# DAPbench-LPC11U35-v1_0_0.net
KiCad netlist of a schematic drawn in EAGLE
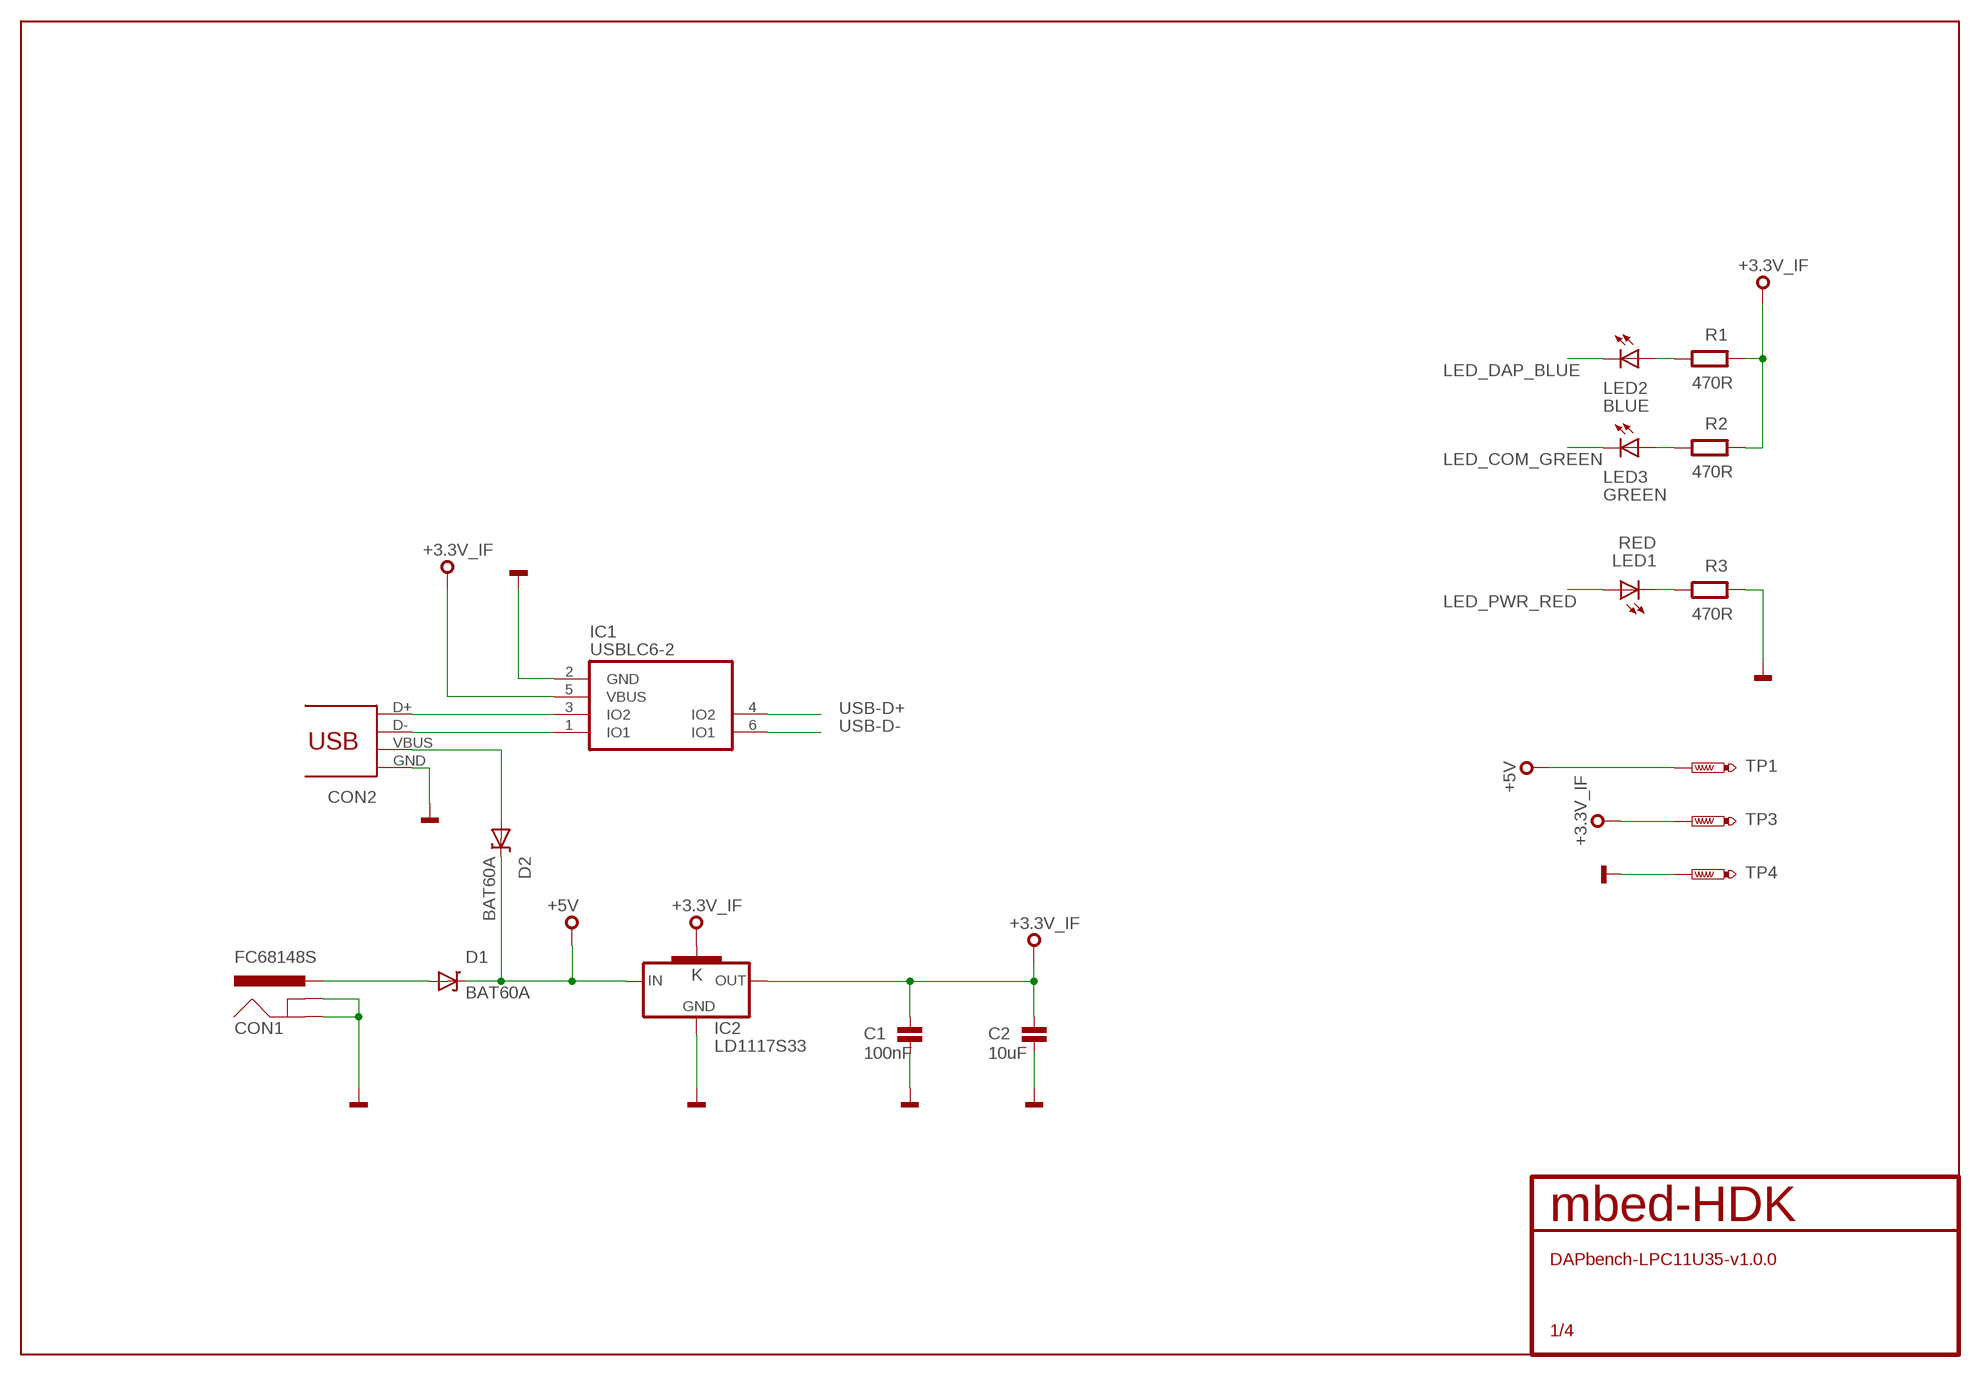
[diagram p0: schematic, sheet 1]
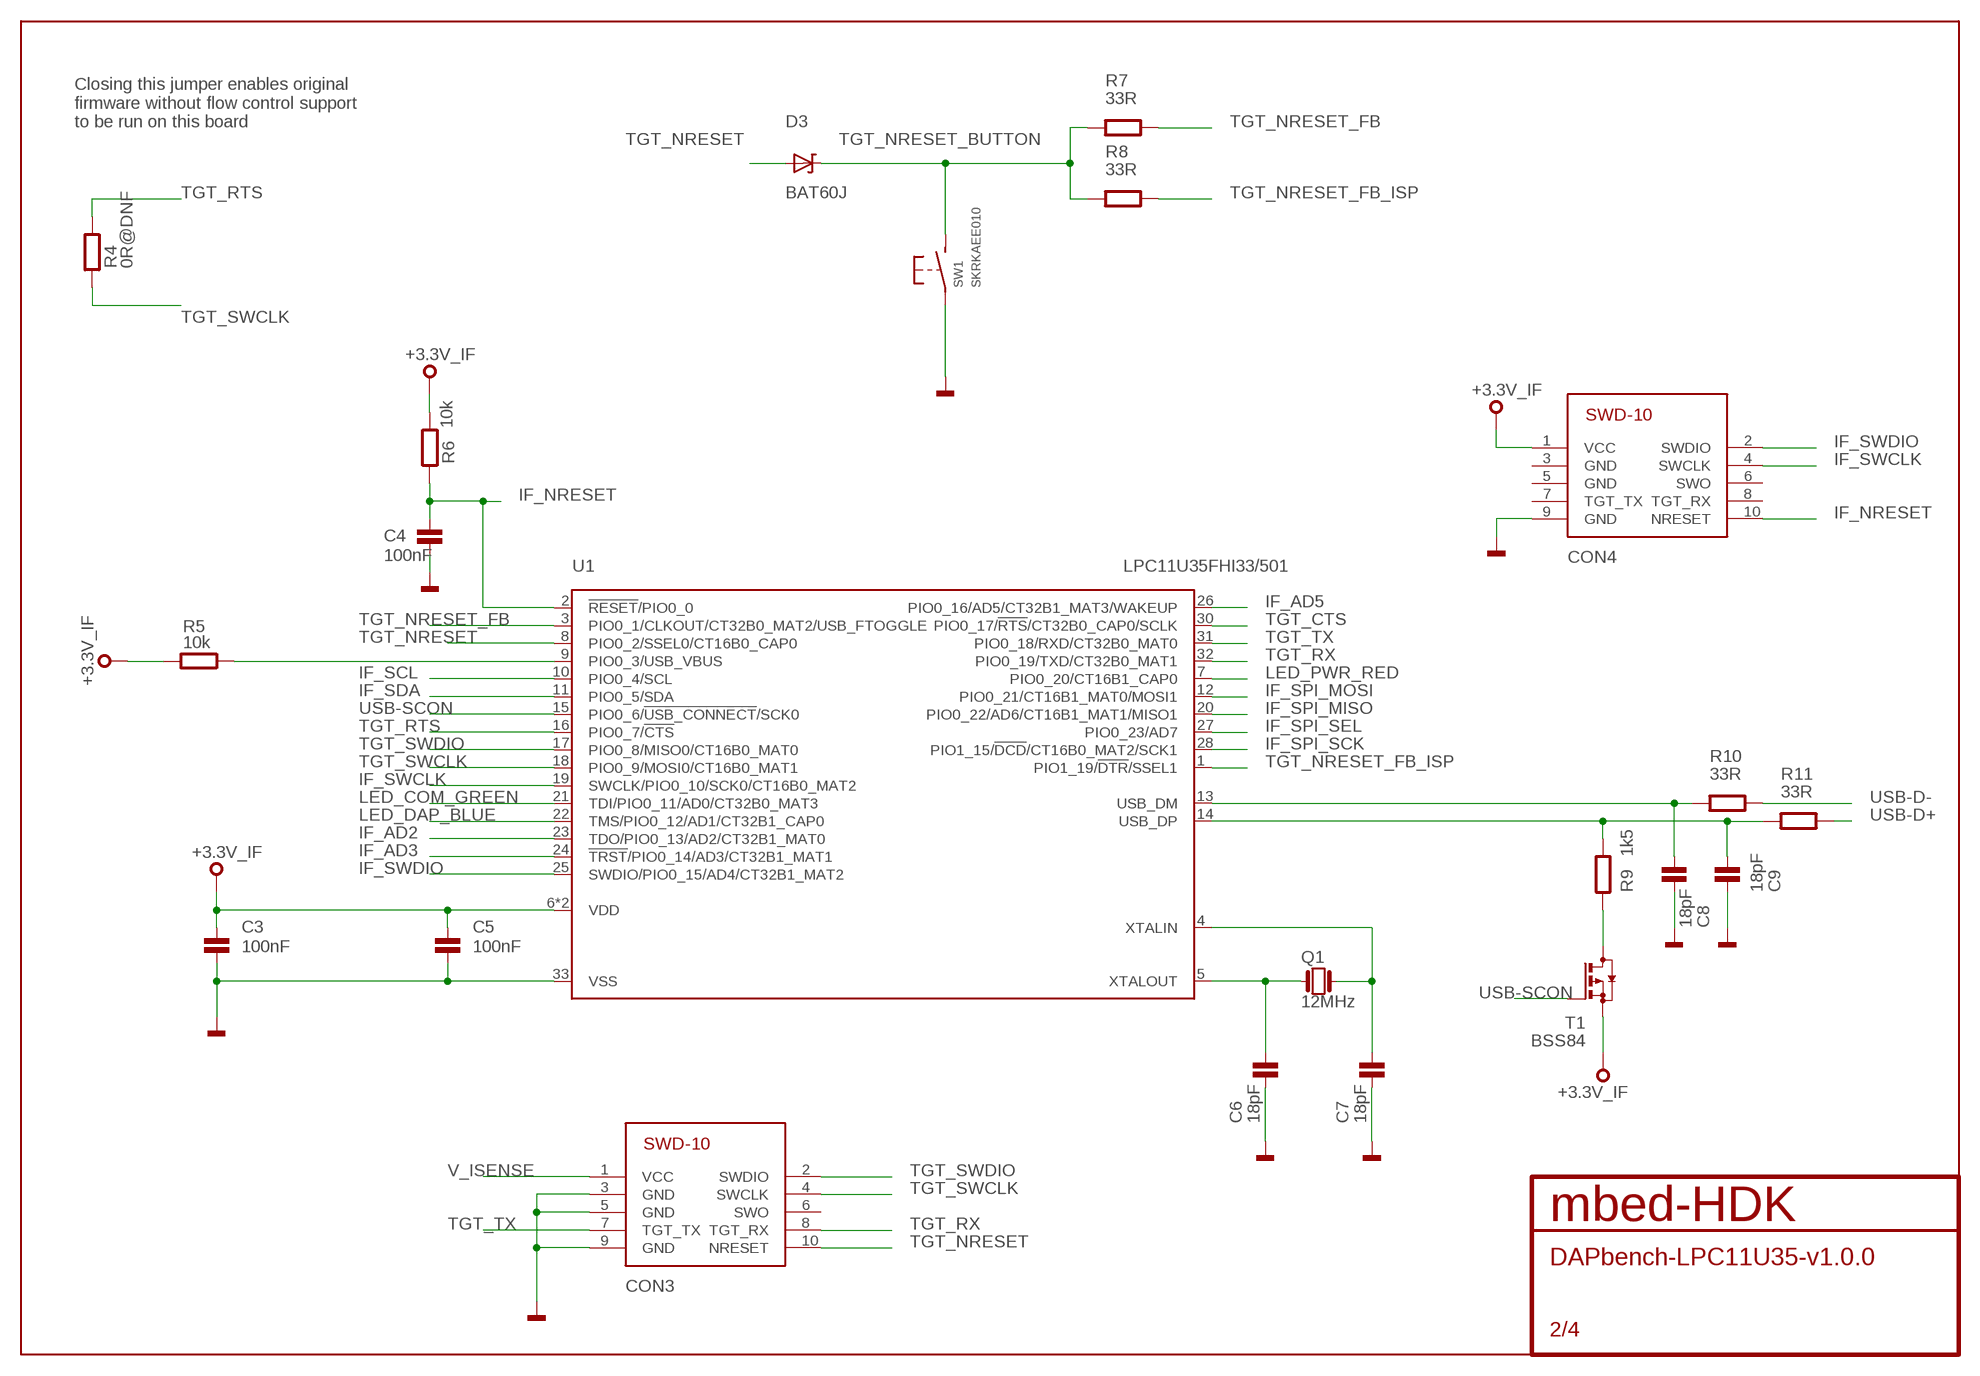
[diagram p1: schematic, sheet 2]
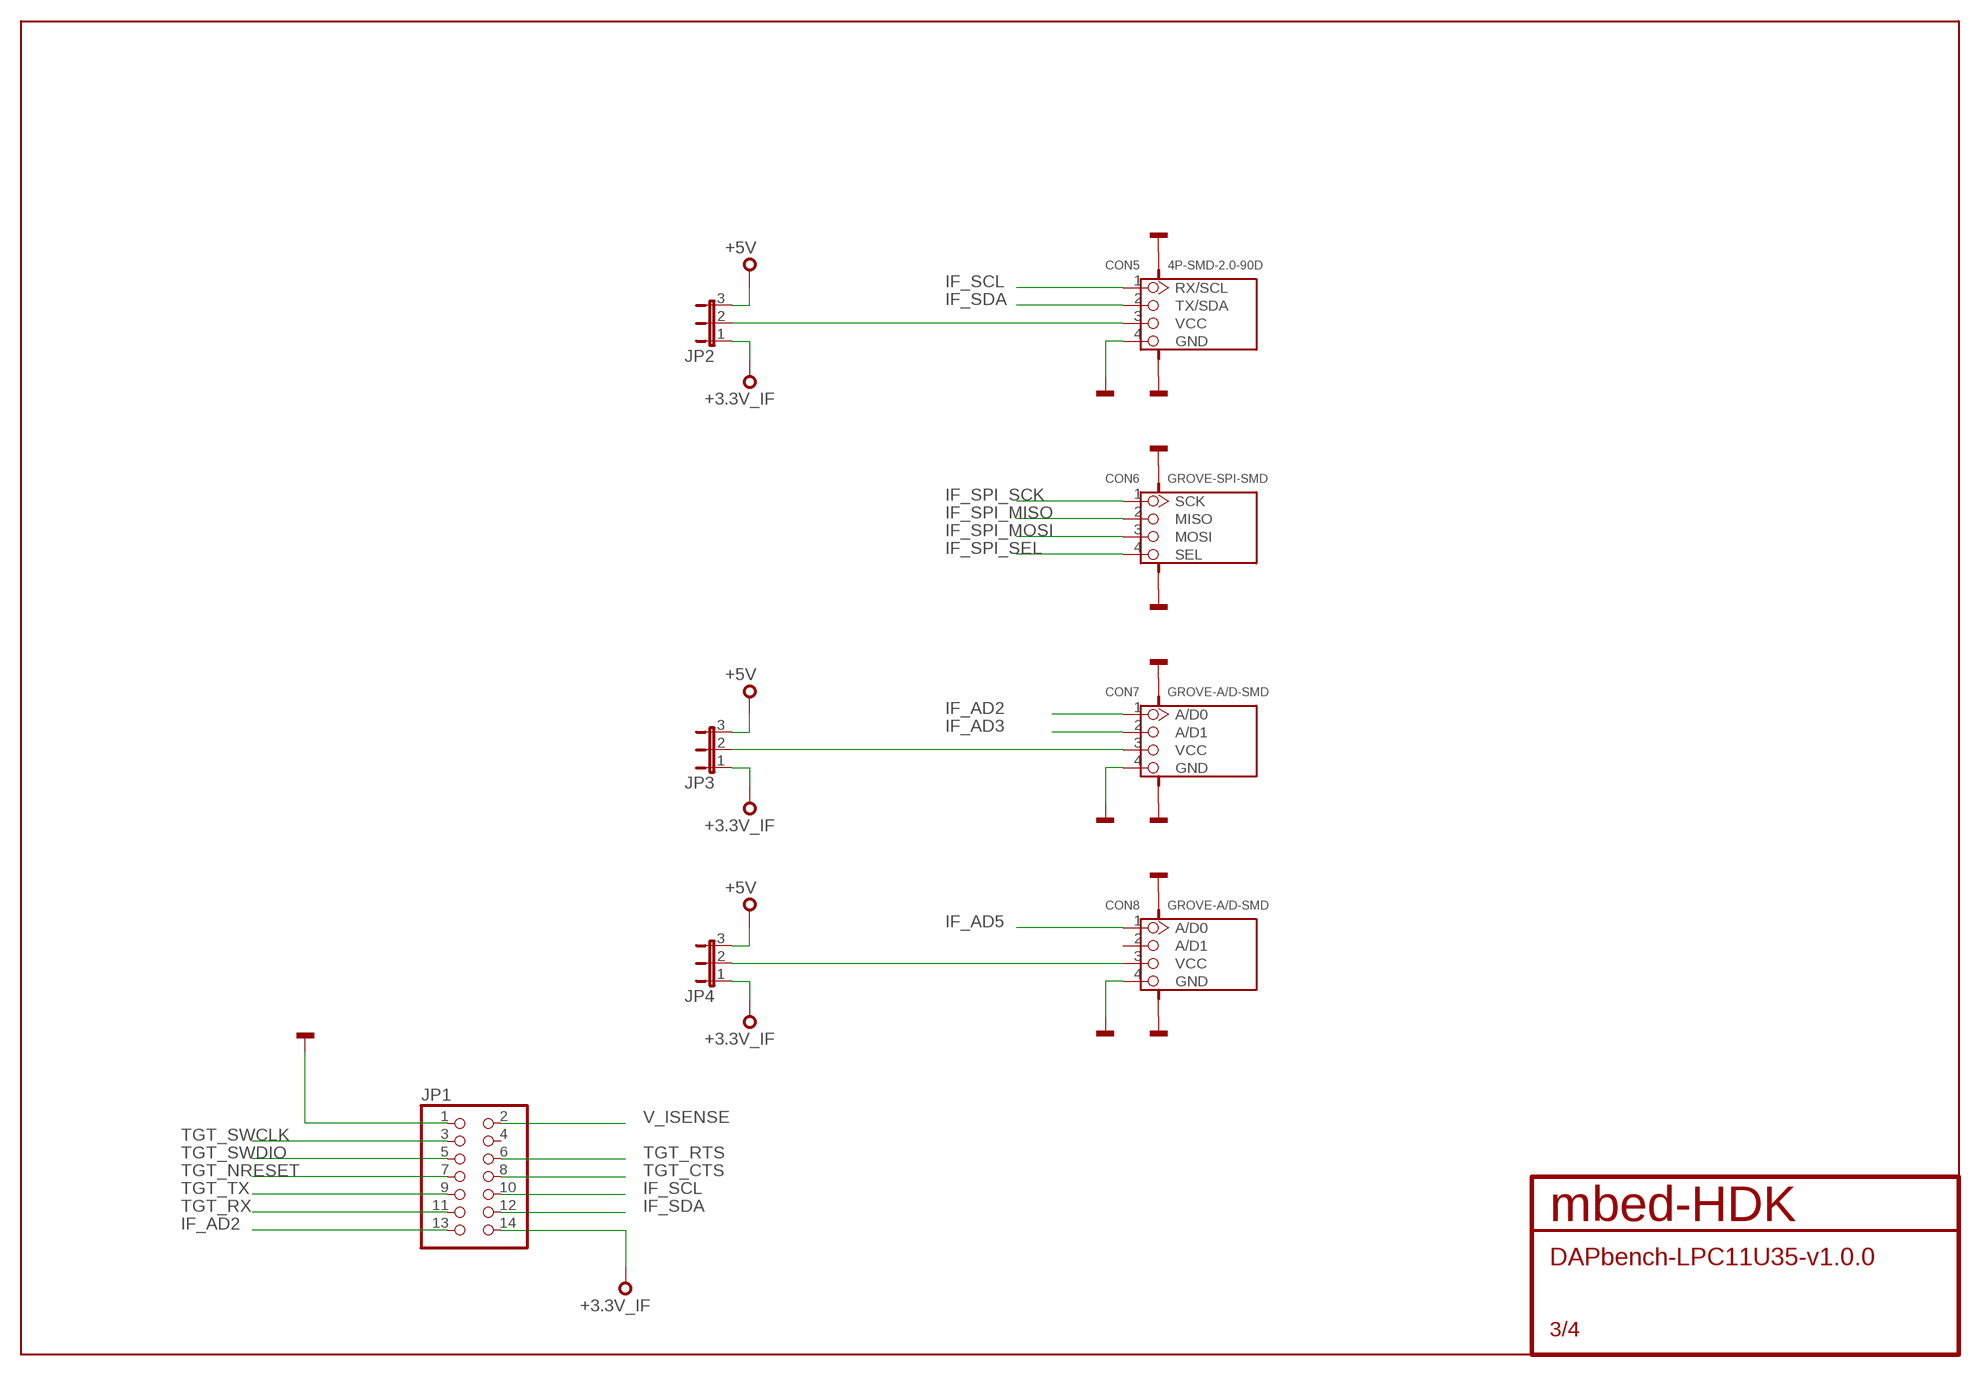
[diagram p2: schematic, sheet 3]
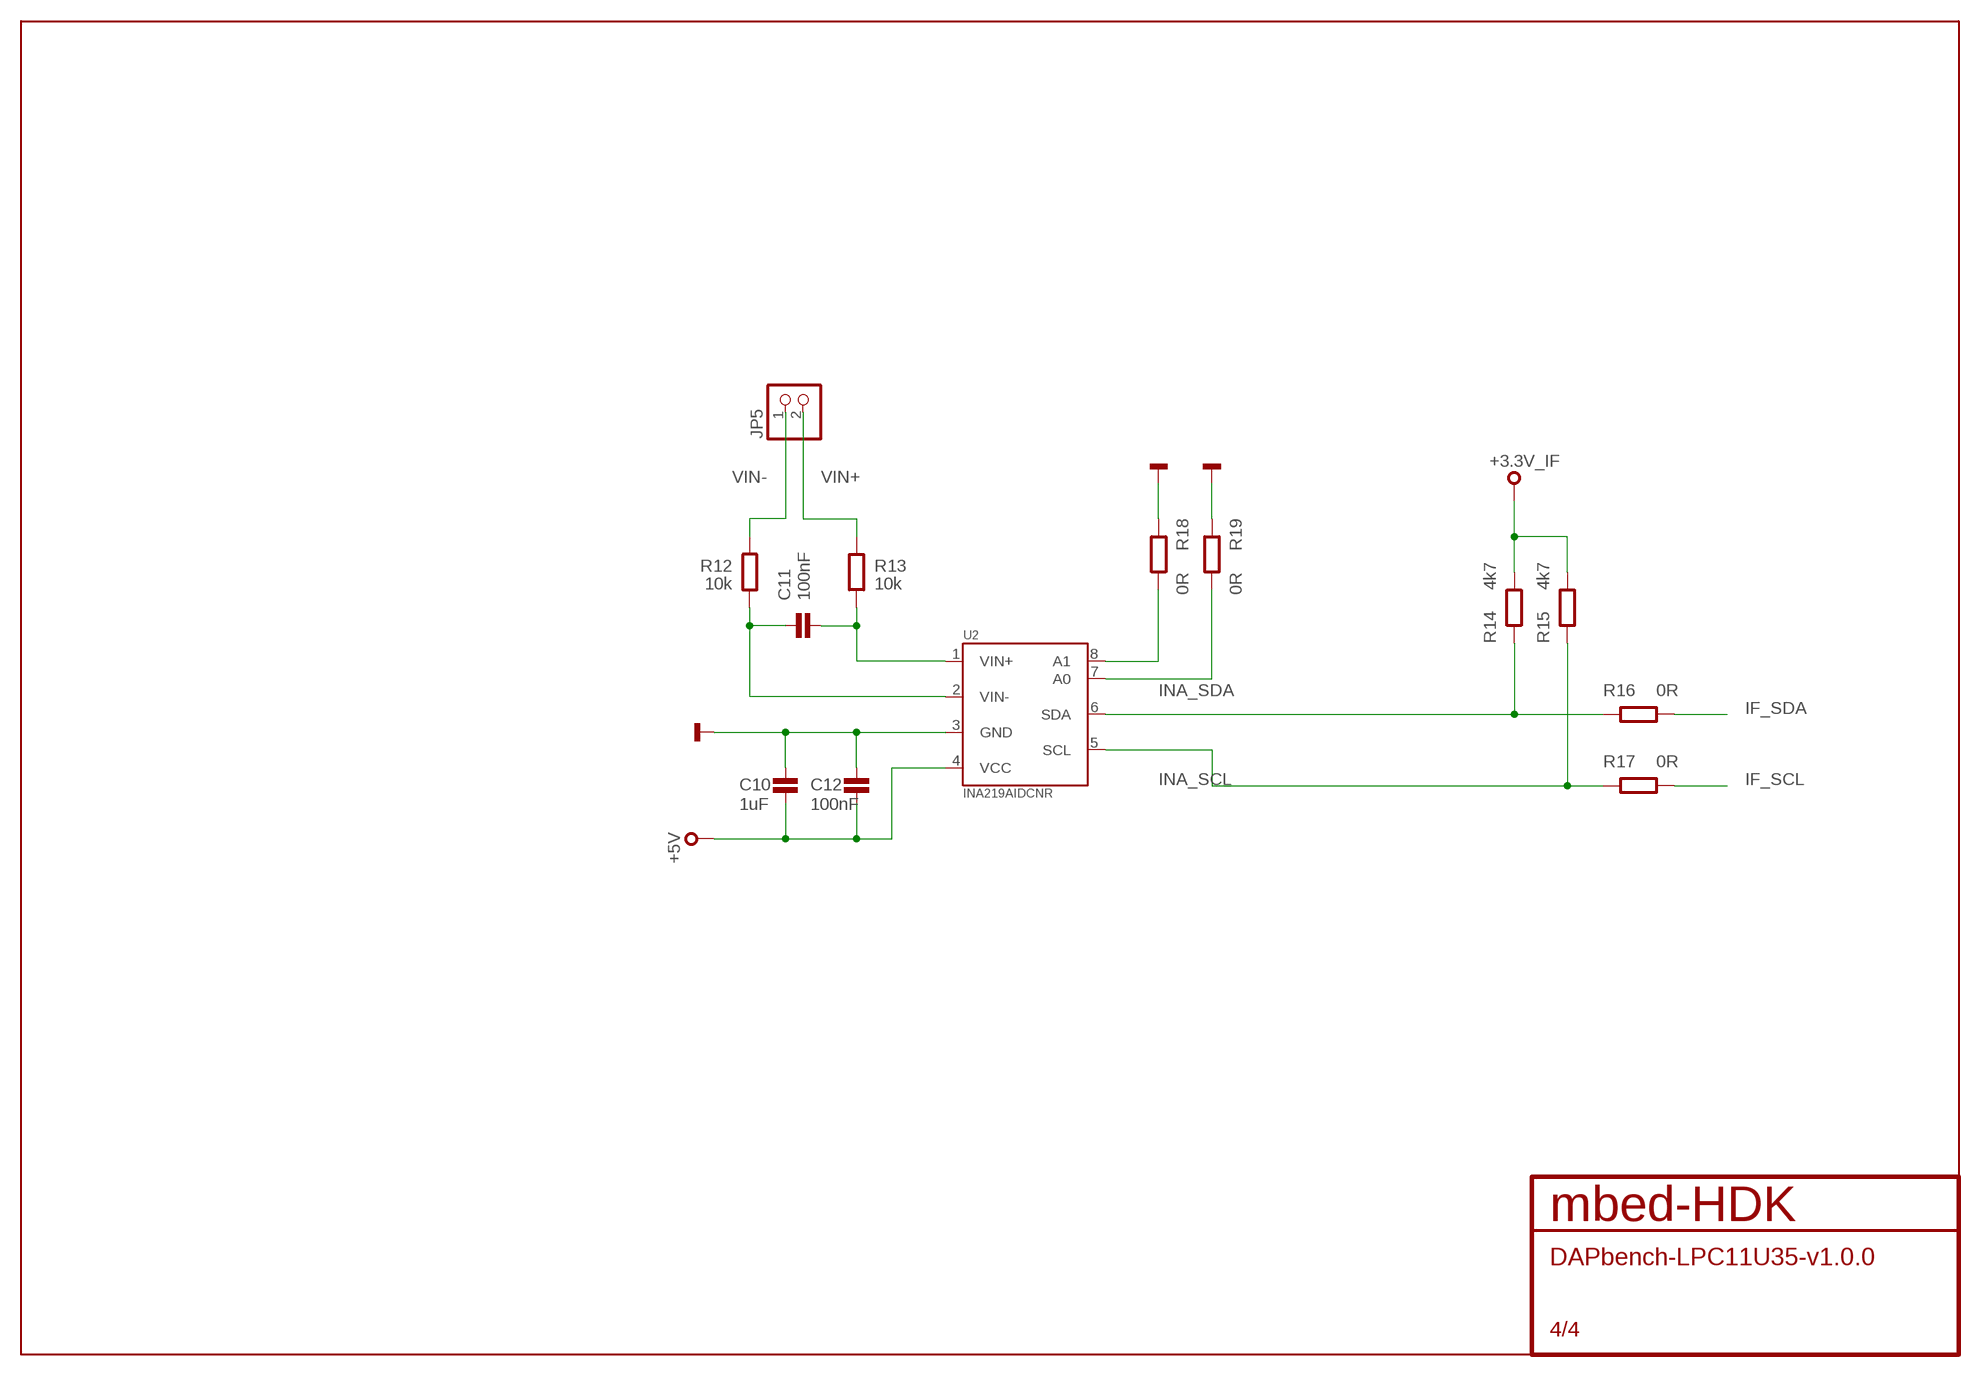
[diagram p3: schematic, sheet 4]

(export (version "E")
  (design (tool "Eeschema 10.0.6"))
  (components
    (comp (ref "C10")
      (value "1uF")
      (footprint "eagle-import:0603")
      (libsource (lib "eagle-import") (part "C0603"))
    )
    (comp (ref "C11")
      (value "100nF")
      (footprint "eagle-import:0603")
      (libsource (lib "eagle-import") (part "C0603"))
    )
    (comp (ref "C12")
      (value "100nF")
      (footprint "eagle-import:0603")
      (libsource (lib "eagle-import") (part "C0603"))
    )
    (comp (ref "JP5")
      (value "PINHD-1X2")
      (footprint "eagle-import:1X02")
      (libsource (lib "eagle-import") (part "PINHD-1X2"))
    )
    (comp (ref "R12")
      (value "10k")
      (footprint "eagle-import:0603@1")
      (libsource (lib "eagle-import") (part "R0603"))
    )
    (comp (ref "R13")
      (value "10k")
      (footprint "eagle-import:0603@1")
      (libsource (lib "eagle-import") (part "R0603"))
    )
    (comp (ref "R14")
      (value "4k7")
      (footprint "eagle-import:0603@1")
      (libsource (lib "eagle-import") (part "R0603"))
    )
    (comp (ref "R15")
      (value "4k7")
      (footprint "eagle-import:0603@1")
      (libsource (lib "eagle-import") (part "R0603"))
    )
    (comp (ref "R16")
      (value "0R")
      (footprint "eagle-import:0603@1")
      (libsource (lib "eagle-import") (part "R0603"))
    )
    (comp (ref "R17")
      (value "0R")
      (footprint "eagle-import:0603@1")
      (libsource (lib "eagle-import") (part "R0603"))
    )
    (comp (ref "R18")
      (value "0R")
      (footprint "eagle-import:0603@1")
      (libsource (lib "eagle-import") (part "R0603"))
    )
    (comp (ref "R19")
      (value "0R")
      (footprint "eagle-import:0603@1")
      (libsource (lib "eagle-import") (part "R0603"))
    )
    (comp (ref "U2")
      (value "INA219AIDCNR")
      (footprint "eagle-import:SOT23-8")
      (fields (field (name "MF") "Texas Instruments"))
      (libsource (lib "eagle-import") (part "INA219AIDCNR"))
    )
    (comp (ref "C1")
      (value "100nF")
      (footprint "eagle-import:0603")
      (libsource (lib "eagle-import") (part "C0603"))
    )
    (comp (ref "C2")
      (value "10uF")
      (footprint "eagle-import:0603")
      (libsource (lib "eagle-import") (part "C0603"))
    )
    (comp (ref "CON1")
      (value "FC68148S")
      (footprint "eagle-import:FC68148S")
      (fields (field (name "MF") "Cliff"))
      (libsource (lib "eagle-import") (part "FC68148S"))
    )
    (comp (ref "CON2")
      (value "USB_MICROB")
      (footprint "eagle-import:MOLEX-47364-0001")
      (libsource (lib "eagle-import") (part "USB_MICROB"))
    )
    (comp (ref "D1")
      (value "BAT60A")
      (footprint "eagle-import:SOD323")
      (fields (field (name "MF") "Infineon"))
      (libsource (lib "eagle-import") (part "mbed-HDK-Transistor_BAT60A"))
    )
    (comp (ref "D2")
      (value "BAT60A")
      (footprint "eagle-import:SOD323")
      (fields (field (name "MF") "Infineon"))
      (libsource (lib "eagle-import") (part "mbed-HDK-Transistor_BAT60A"))
    )
    (comp (ref "IC1")
      (value "USBLC6-2SC6")
      (footprint "eagle-import:SOT23-6L")
      (libsource (lib "eagle-import") (part "USBLC6-2SC6"))
    )
    (comp (ref "IC2")
      (value "LD1117S33")
      (footprint "eagle-import:SOT223")
      (libsource (lib "eagle-import") (part "LD1117S33"))
    )
    (comp (ref "LED1")
      (value "RED")
      (footprint "eagle-import:CHIPLED_0603")
      (libsource (lib "eagle-import") (part "LED0603"))
    )
    (comp (ref "LED2")
      (value "BLUE")
      (footprint "eagle-import:CHIPLED_0603")
      (libsource (lib "eagle-import") (part "LED0603"))
    )
    (comp (ref "LED3")
      (value "GREEN")
      (footprint "eagle-import:CHIPLED_0603")
      (libsource (lib "eagle-import") (part "LED0603"))
    )
    (comp (ref "R1")
      (value "470R")
      (footprint "eagle-import:0603@1")
      (libsource (lib "eagle-import") (part "R0603"))
    )
    (comp (ref "R2")
      (value "470R")
      (footprint "eagle-import:0603@1")
      (libsource (lib "eagle-import") (part "R0603"))
    )
    (comp (ref "R3")
      (value "470R")
      (footprint "eagle-import:0603@1")
      (libsource (lib "eagle-import") (part "R0603"))
    )
    (comp (ref "TP1")
      (value "TEST-POINT-50R-PTH")
      (footprint "eagle-import:TP50-PTH")
      (libsource (lib "eagle-import") (part "TEST-POINT-50R-PTH"))
    )
    (comp (ref "TP3")
      (value "TEST-POINT-50R-PTH")
      (footprint "eagle-import:TP50-PTH")
      (libsource (lib "eagle-import") (part "TEST-POINT-50R-PTH"))
    )
    (comp (ref "TP4")
      (value "TEST-POINT-50R-PTH")
      (footprint "eagle-import:TP50-PTH")
      (libsource (lib "eagle-import") (part "TEST-POINT-50R-PTH"))
    )
    (comp (ref "CON5")
      (value "4P-SMD-2.0-90D")
      (footprint "eagle-import:HW4-SMD-2.0-90D")
      (libsource (lib "eagle-import") (part "GROVE-UART-I2C-SMD"))
    )
    (comp (ref "CON6")
      (value "GROVE-SPI-SMD")
      (footprint "eagle-import:HW4-SMD-2.0-90D")
      (libsource (lib "eagle-import") (part "GROVE-SPI-SMD"))
    )
    (comp (ref "CON7")
      (value "GROVE-A/D-SMD")
      (footprint "eagle-import:HW4-SMD-2.0-90D")
      (libsource (lib "eagle-import") (part "GROVE-A/D-SMD"))
    )
    (comp (ref "CON8")
      (value "GROVE-A/D-SMD")
      (footprint "eagle-import:HW4-SMD-2.0-90D")
      (libsource (lib "eagle-import") (part "GROVE-A/D-SMD"))
    )
    (comp (ref "JP1")
      (value "PINHD-2X7")
      (footprint "eagle-import:2X07")
      (libsource (lib "eagle-import") (part "PINHD-2X7"))
    )
    (comp (ref "JP2")
      (value "JP2E")
      (footprint "eagle-import:JP2")
      (libsource (lib "eagle-import") (part "JP2E"))
    )
    (comp (ref "JP3")
      (value "JP2E")
      (footprint "eagle-import:JP2")
      (libsource (lib "eagle-import") (part "JP2E"))
    )
    (comp (ref "JP4")
      (value "JP2E")
      (footprint "eagle-import:JP2")
      (libsource (lib "eagle-import") (part "JP2E"))
    )
    (comp (ref "C3")
      (value "100nF")
      (footprint "eagle-import:0603")
      (libsource (lib "eagle-import") (part "C0603"))
    )
    (comp (ref "C4")
      (value "100nF")
      (footprint "eagle-import:0603")
      (libsource (lib "eagle-import") (part "C0603"))
    )
    (comp (ref "C5")
      (value "100nF")
      (footprint "eagle-import:0603")
      (libsource (lib "eagle-import") (part "C0603"))
    )
    (comp (ref "C6")
      (value "18pF")
      (footprint "eagle-import:0603")
      (libsource (lib "eagle-import") (part "C0603"))
    )
    (comp (ref "C7")
      (value "18pF")
      (footprint "eagle-import:0603")
      (libsource (lib "eagle-import") (part "C0603"))
    )
    (comp (ref "C8")
      (value "18pF")
      (footprint "eagle-import:0603")
      (libsource (lib "eagle-import") (part "C0603"))
    )
    (comp (ref "C9")
      (value "18pF")
      (footprint "eagle-import:0603")
      (libsource (lib "eagle-import") (part "C0603"))
    )
    (comp (ref "CON3")
      (value "SWD-10/TC2050_SMD")
      (footprint "eagle-import:FTSH-105-02")
      (libsource (lib "eagle-import") (part "SWD-10/TC2050_SMD"))
    )
    (comp (ref "CON4")
      (value "SWD-10/TC2050_SMD")
      (footprint "eagle-import:FTSH-105-02")
      (libsource (lib "eagle-import") (part "SWD-10/TC2050_SMD"))
    )
    (comp (ref "D3")
      (value "BAT60J")
      (footprint "eagle-import:BAT60A")
      (libsource (lib "eagle-import") (part "BAT60A"))
    )
    (comp (ref "Q1")
      (value "12MHz")
      (footprint "eagle-import:3.2X.2.5")
      (libsource (lib "eagle-import") (part "Q_3.2X2.5"))
    )
    (comp (ref "R4")
      (value "0R@DNF")
      (footprint "eagle-import:0402@1")
      (libsource (lib "eagle-import") (part "R0402"))
    )
    (comp (ref "R5")
      (value "10k")
      (footprint "eagle-import:0603@1")
      (libsource (lib "eagle-import") (part "R0603"))
    )
    (comp (ref "R6")
      (value "10k")
      (footprint "eagle-import:0603@1")
      (libsource (lib "eagle-import") (part "R0603"))
    )
    (comp (ref "R7")
      (value "33R")
      (footprint "eagle-import:0603@1")
      (libsource (lib "eagle-import") (part "R0603"))
    )
    (comp (ref "R8")
      (value "33R")
      (footprint "eagle-import:0603@1")
      (libsource (lib "eagle-import") (part "R0603"))
    )
    (comp (ref "R9")
      (value "1k5")
      (footprint "eagle-import:0603@1")
      (libsource (lib "eagle-import") (part "R0603"))
    )
    (comp (ref "R10")
      (value "33R")
      (footprint "eagle-import:0603@1")
      (libsource (lib "eagle-import") (part "R0603"))
    )
    (comp (ref "R11")
      (value "33R")
      (footprint "eagle-import:0603@1")
      (libsource (lib "eagle-import") (part "R0603"))
    )
    (comp (ref "SW1")
      (value "SKRKAEE010")
      (footprint "eagle-import:SKRKAEE010")
      (fields (field (name "MF") "ALPS"))
      (libsource (lib "eagle-import") (part "SKRKAEE010"))
    )
    (comp (ref "T1")
      (value "BSS84")
      (footprint "eagle-import:SOT23")
      (libsource (lib "eagle-import") (part "BSS84"))
    )
    (comp (ref "U1")
      (value "LPC11U35FHI33/501")
      (footprint "eagle-import:SOT617-3")
      (fields (field (name "MF") "NXP"))
      (libsource (lib "eagle-import") (part "LPC11U35FHI33/501"))
    )
  )
  (nets
    (net (code "1") (name "+3.3V_IF") (class "Default")
      (node (ref "C1") (pin "1") (pinfunction "P$1_1") (pintype "passive"))
      (node (ref "C2") (pin "1") (pinfunction "P$1_1") (pintype "passive"))
      (node (ref "C3") (pin "1") (pinfunction "P$1_1") (pintype "passive"))
      (node (ref "C5") (pin "1") (pinfunction "P$1_1") (pintype "passive"))
      (node (ref "CON4") (pin "1") (pinfunction "VCC_1") (pintype "bidirectional"))
      (node (ref "IC1") (pin "5") (pinfunction "VBUS_5") (pintype "bidirectional"))
      (node (ref "IC2") (pin "2") (pinfunction "OUT_2") (pintype "passive"))
      (node (ref "IC2") (pin "4") (pinfunction "K_4") (pintype "passive"))
      (node (ref "JP1") (pin "14") (pinfunction "14_14") (pintype "passive"))
      (node (ref "JP2") (pin "1") (pinfunction "1_1") (pintype "passive"))
      (node (ref "JP3") (pin "1") (pinfunction "1_1") (pintype "passive"))
      (node (ref "JP4") (pin "1") (pinfunction "1_1") (pintype "passive"))
      (node (ref "R1") (pin "1") (pinfunction "P$1_1") (pintype "passive"))
      (node (ref "R14") (pin "1") (pinfunction "P$1_1") (pintype "passive"))
      (node (ref "R15") (pin "1") (pinfunction "P$1_1") (pintype "passive"))
      (node (ref "R2") (pin "1") (pinfunction "P$1_1") (pintype "passive"))
      (node (ref "R5") (pin "2") (pinfunction "P$2_2") (pintype "passive"))
      (node (ref "R6") (pin "2") (pinfunction "P$2_2") (pintype "passive"))
      (node (ref "T1") (pin "2") (pinfunction "S_2") (pintype "passive"))
      (node (ref "TP3") (pin "TP") (pinfunction "TP_TP") (pintype "input"))
      (node (ref "U1") (pin "29") (pinfunction "VDD_29") (pintype "passive"))
      (node (ref "U1") (pin "6") (pinfunction "VDD_6") (pintype "passive"))
    )
    (net (code "2") (name "+5V") (class "Default")
      (node (ref "C10") (pin "2") (pinfunction "P$2_2") (pintype "passive"))
      (node (ref "C12") (pin "2") (pinfunction "P$2_2") (pintype "passive"))
      (node (ref "D1") (pin "K") (pinfunction "K_K") (pintype "passive"))
      (node (ref "D2") (pin "K") (pinfunction "K_K") (pintype "passive"))
      (node (ref "IC2") (pin "3") (pinfunction "IN_3") (pintype "input"))
      (node (ref "JP2") (pin "3") (pinfunction "3_3") (pintype "passive"))
      (node (ref "JP3") (pin "3") (pinfunction "3_3") (pintype "passive"))
      (node (ref "JP4") (pin "3") (pinfunction "3_3") (pintype "passive"))
      (node (ref "TP1") (pin "TP") (pinfunction "TP_TP") (pintype "input"))
      (node (ref "U2") (pin "4") (pinfunction "VCC_4") (pintype "power_in"))
    )
    (net (code "3") (name "GND") (class "Default")
      (node (ref "C1") (pin "2") (pinfunction "P$2_2") (pintype "passive"))
      (node (ref "C10") (pin "1") (pinfunction "P$1_1") (pintype "passive"))
      (node (ref "C12") (pin "1") (pinfunction "P$1_1") (pintype "passive"))
      (node (ref "C2") (pin "2") (pinfunction "P$2_2") (pintype "passive"))
      (node (ref "C3") (pin "2") (pinfunction "P$2_2") (pintype "passive"))
      (node (ref "C4") (pin "2") (pinfunction "P$2_2") (pintype "passive"))
      (node (ref "C5") (pin "2") (pinfunction "P$2_2") (pintype "passive"))
      (node (ref "C6") (pin "2") (pinfunction "P$2_2") (pintype "passive"))
      (node (ref "C7") (pin "2") (pinfunction "P$2_2") (pintype "passive"))
      (node (ref "C8") (pin "2") (pinfunction "P$2_2") (pintype "passive"))
      (node (ref "C9") (pin "2") (pinfunction "P$2_2") (pintype "passive"))
      (node (ref "CON1") (pin "2") (pinfunction "GNDBREAK_2") (pintype "bidirectional"))
      (node (ref "CON1") (pin "3") (pinfunction "GND_3") (pintype "bidirectional"))
      (node (ref "CON2") (pin "GND") (pinfunction "GND_GND") (pintype "bidirectional"))
      (node (ref "CON3") (pin "3") (pinfunction "GND_3") (pintype "bidirectional"))
      (node (ref "CON3") (pin "5") (pinfunction "GND_5") (pintype "bidirectional"))
      (node (ref "CON3") (pin "9") (pinfunction "GND_9") (pintype "bidirectional"))
      (node (ref "CON4") (pin "9") (pinfunction "GND_9") (pintype "bidirectional"))
      (node (ref "CON5") (pin "4") (pinfunction "GND_4") (pintype "bidirectional"))
      (node (ref "CON5") (pin "SS1") (pinfunction "SS1_SS1") (pintype "bidirectional"))
      (node (ref "CON5") (pin "SS2") (pinfunction "SS2_SS2") (pintype "bidirectional"))
      (node (ref "CON6") (pin "SS1") (pinfunction "SS1_SS1") (pintype "bidirectional"))
      (node (ref "CON6") (pin "SS2") (pinfunction "SS2_SS2") (pintype "bidirectional"))
      (node (ref "CON7") (pin "4") (pinfunction "GND_4") (pintype "bidirectional"))
      (node (ref "CON7") (pin "SS1") (pinfunction "SS1_SS1") (pintype "bidirectional"))
      (node (ref "CON7") (pin "SS2") (pinfunction "SS2_SS2") (pintype "bidirectional"))
      (node (ref "CON8") (pin "4") (pinfunction "GND_4") (pintype "bidirectional"))
      (node (ref "CON8") (pin "SS1") (pinfunction "SS1_SS1") (pintype "bidirectional"))
      (node (ref "CON8") (pin "SS2") (pinfunction "SS2_SS2") (pintype "bidirectional"))
      (node (ref "IC1") (pin "2") (pinfunction "GND_2") (pintype "bidirectional"))
      (node (ref "IC2") (pin "1") (pinfunction "GND_1") (pintype "input"))
      (node (ref "JP1") (pin "1") (pinfunction "1_1") (pintype "passive"))
      (node (ref "R18") (pin "2") (pinfunction "P$2_2") (pintype "passive"))
      (node (ref "R19") (pin "2") (pinfunction "P$2_2") (pintype "passive"))
      (node (ref "R3") (pin "1") (pinfunction "P$1_1") (pintype "passive"))
      (node (ref "SW1") (pin "P$1") (pinfunction "P_P$1") (pintype "passive"))
      (node (ref "TP4") (pin "TP") (pinfunction "TP_TP") (pintype "input"))
      (node (ref "U1") (pin "33") (pinfunction "VSS_33") (pintype "passive"))
      (node (ref "U2") (pin "3") (pinfunction "GND_3") (pintype "power_in"))
    )
    (net (code "4") (name "IF_AD2") (class "Default")
      (node (ref "CON7") (pin "1") (pinfunction "A/D0_1") (pintype "bidirectional"))
      (node (ref "JP1") (pin "13") (pinfunction "13_13") (pintype "passive"))
      (node (ref "U1") (pin "23") (pinfunction "TDO/PIO0_13/AD2/CT32B1_MAT0_23") (pintype "bidirectional"))
    )
    (net (code "5") (name "IF_AD3") (class "Default")
      (node (ref "CON7") (pin "2") (pinfunction "A/D1_2") (pintype "bidirectional"))
      (node (ref "U1") (pin "24") (pinfunction "~{TRST}/PIO0_14/AD3/CT32B1_MAT1_24") (pintype "bidirectional"))
    )
    (net (code "6") (name "IF_AD5") (class "Default")
      (node (ref "CON8") (pin "1") (pinfunction "A/D0_1") (pintype "bidirectional"))
      (node (ref "U1") (pin "26") (pinfunction "PIO0_16/AD5/CT32B1_MAT3/WAKEUP_26") (pintype "bidirectional"))
    )
    (net (code "7") (name "IF_NRESET") (class "Default")
      (node (ref "C4") (pin "1") (pinfunction "P$1_1") (pintype "passive"))
      (node (ref "CON4") (pin "10") (pinfunction "NRESET_10") (pintype "bidirectional"))
      (node (ref "R6") (pin "1") (pinfunction "P$1_1") (pintype "passive"))
      (node (ref "U1") (pin "2") (pinfunction "~{RESET}/PIO0_0_2") (pintype "bidirectional"))
    )
    (net (code "8") (name "IF_SCL") (class "Default")
      (node (ref "CON5") (pin "1") (pinfunction "RX/SCL_1") (pintype "bidirectional"))
      (node (ref "JP1") (pin "10") (pinfunction "10_10") (pintype "passive"))
      (node (ref "R17") (pin "1") (pinfunction "P$1_1") (pintype "passive"))
      (node (ref "U1") (pin "10") (pinfunction "PIO0_4/SCL_10") (pintype "bidirectional"))
    )
    (net (code "9") (name "IF_SDA") (class "Default")
      (node (ref "CON5") (pin "2") (pinfunction "TX/SDA_2") (pintype "bidirectional"))
      (node (ref "JP1") (pin "12") (pinfunction "12_12") (pintype "passive"))
      (node (ref "R16") (pin "1") (pinfunction "P$1_1") (pintype "passive"))
      (node (ref "U1") (pin "11") (pinfunction "PIO0_5/SDA_11") (pintype "bidirectional"))
    )
    (net (code "10") (name "IF_SPI_MISO") (class "Default")
      (node (ref "CON6") (pin "2") (pinfunction "MISO_2") (pintype "bidirectional"))
      (node (ref "U1") (pin "20") (pinfunction "PIO0_22/AD6/CT16B1_MAT1/MISO1_20") (pintype "bidirectional"))
    )
    (net (code "11") (name "IF_SPI_MOSI") (class "Default")
      (node (ref "CON6") (pin "3") (pinfunction "MOSI_3") (pintype "bidirectional"))
      (node (ref "U1") (pin "12") (pinfunction "PIO0_21/CT16B1_MAT0/MOSI1_12") (pintype "bidirectional"))
    )
    (net (code "12") (name "IF_SPI_SCK") (class "Default")
      (node (ref "CON6") (pin "1") (pinfunction "SCK_1") (pintype "bidirectional"))
      (node (ref "U1") (pin "28") (pinfunction "PIO1_15/~{DCD}/CT16B0_MAT2/SCK1_28") (pintype "bidirectional"))
    )
    (net (code "13") (name "IF_SPI_SEL") (class "Default")
      (node (ref "CON6") (pin "4") (pinfunction "SEL_4") (pintype "bidirectional"))
      (node (ref "U1") (pin "27") (pinfunction "PIO0_23/AD7_27") (pintype "bidirectional"))
    )
    (net (code "14") (name "IF_SWCLK") (class "Default")
      (node (ref "CON4") (pin "4") (pinfunction "SWCLK_4") (pintype "bidirectional"))
      (node (ref "U1") (pin "19") (pinfunction "SWCLK/PIO0_10/SCK0/CT16B0_MAT2_19") (pintype "bidirectional"))
    )
    (net (code "15") (name "IF_SWDIO") (class "Default")
      (node (ref "CON4") (pin "2") (pinfunction "SWDIO_2") (pintype "bidirectional"))
      (node (ref "U1") (pin "25") (pinfunction "SWDIO/PIO0_15/AD4/CT32B1_MAT2_25") (pintype "bidirectional"))
    )
    (net (code "16") (name "INA_SCL") (class "Default")
      (node (ref "R15") (pin "2") (pinfunction "P$2_2") (pintype "passive"))
      (node (ref "R17") (pin "2") (pinfunction "P$2_2") (pintype "passive"))
      (node (ref "U2") (pin "5") (pinfunction "SCL_5") (pintype "bidirectional"))
    )
    (net (code "17") (name "INA_SDA") (class "Default")
      (node (ref "R14") (pin "2") (pinfunction "P$2_2") (pintype "passive"))
      (node (ref "R16") (pin "2") (pinfunction "P$2_2") (pintype "passive"))
      (node (ref "U2") (pin "6") (pinfunction "SDA_6") (pintype "bidirectional"))
    )
    (net (code "18") (name "LED_COM_GREEN") (class "Default")
      (node (ref "LED3") (pin "C") (pinfunction "C_C") (pintype "passive"))
      (node (ref "U1") (pin "21") (pinfunction "TDI/PIO0_11/AD0/CT32B0_MAT3_21") (pintype "bidirectional"))
    )
    (net (code "19") (name "LED_DAP_BLUE") (class "Default")
      (node (ref "LED2") (pin "C") (pinfunction "C_C") (pintype "passive"))
      (node (ref "U1") (pin "22") (pinfunction "TMS/PIO0_12/AD1/CT32B1_CAP0_22") (pintype "bidirectional"))
    )
    (net (code "20") (name "LED_PWR_RED") (class "Default")
      (node (ref "LED1") (pin "A") (pinfunction "A_A") (pintype "passive"))
      (node (ref "U1") (pin "7") (pinfunction "PIO0_20/CT16B1_CAP0_7") (pintype "bidirectional"))
    )
    (net (code "21") (name "Net-(C6-P$1)") (class "Default")
      (node (ref "C6") (pin "1") (pinfunction "P$1_1") (pintype "passive"))
      (node (ref "Q1") (pin "P$1") (pinfunction "1_P$1") (pintype "passive"))
      (node (ref "U1") (pin "5") (pinfunction "XTALOUT_5") (pintype "output"))
    )
    (net (code "22") (name "Net-(C7-P$1)") (class "Default")
      (node (ref "C7") (pin "1") (pinfunction "P$1_1") (pintype "passive"))
      (node (ref "Q1") (pin "P$3") (pinfunction "2_P$3") (pintype "passive"))
      (node (ref "U1") (pin "4") (pinfunction "XTALIN_4") (pintype "input"))
    )
    (net (code "23") (name "Net-(C8-P$1)") (class "Default")
      (node (ref "C8") (pin "1") (pinfunction "P$1_1") (pintype "passive"))
      (node (ref "R10") (pin "2") (pinfunction "P$2_2") (pintype "passive"))
      (node (ref "U1") (pin "13") (pinfunction "USB_DM_13") (pintype "bidirectional"))
    )
    (net (code "24") (name "Net-(C9-P$1)") (class "Default")
      (node (ref "C9") (pin "1") (pinfunction "P$1_1") (pintype "passive"))
      (node (ref "R11") (pin "2") (pinfunction "P$2_2") (pintype "passive"))
      (node (ref "R9") (pin "2") (pinfunction "P$2_2") (pintype "passive"))
      (node (ref "U1") (pin "14") (pinfunction "USB_DP_14") (pintype "bidirectional"))
    )
    (net (code "25") (name "Net-(C11-P$1)") (class "Default")
      (node (ref "C11") (pin "1") (pinfunction "P$1_1") (pintype "passive"))
      (node (ref "R13") (pin "1") (pinfunction "P$1_1") (pintype "passive"))
      (node (ref "U2") (pin "1") (pinfunction "VIN+_1") (pintype "input"))
    )
    (net (code "26") (name "Net-(C11-P$2)") (class "Default")
      (node (ref "C11") (pin "2") (pinfunction "P$2_2") (pintype "passive"))
      (node (ref "R12") (pin "1") (pinfunction "P$1_1") (pintype "passive"))
      (node (ref "U2") (pin "2") (pinfunction "VIN-_2") (pintype "input"))
    )
    (net (code "27") (name "Net-(CON1-PWR-Pad1-1)") (class "Default")
      (node (ref "CON1") (pin "1-1") (pinfunction "PWR_1-1") (pintype "bidirectional"))
      (node (ref "CON1") (pin "1-2") (pinfunction "PWR_1-2") (pintype "bidirectional"))
      (node (ref "D1") (pin "A") (pinfunction "A_A") (pintype "passive"))
    )
    (net (code "28") (name "Net-(CON2-PadD+)") (class "Default")
      (node (ref "CON2") (pin "D+") (pinfunction "D+_D+") (pintype "bidirectional"))
      (node (ref "IC1") (pin "3") (pinfunction "IO2_3") (pintype "bidirectional"))
    )
    (net (code "29") (name "Net-(CON2-PadD-)") (class "Default")
      (node (ref "CON2") (pin "D-") (pinfunction "D-_D-") (pintype "bidirectional"))
      (node (ref "IC1") (pin "1") (pinfunction "IO1_1") (pintype "bidirectional"))
    )
    (net (code "30") (name "Net-(CON2-PadVBUS)") (class "Default")
      (node (ref "CON2") (pin "VBUS") (pinfunction "VBUS_VBUS") (pintype "bidirectional"))
      (node (ref "D2") (pin "A") (pinfunction "A_A") (pintype "passive"))
    )
    (net (code "31") (name "Net-(CON5-VCC)") (class "Default")
      (node (ref "CON5") (pin "3") (pinfunction "VCC_3") (pintype "bidirectional"))
      (node (ref "JP2") (pin "2") (pinfunction "2_2") (pintype "passive"))
    )
    (net (code "32") (name "Net-(CON7-VCC)") (class "Default")
      (node (ref "CON7") (pin "3") (pinfunction "VCC_3") (pintype "bidirectional"))
      (node (ref "JP3") (pin "2") (pinfunction "2_2") (pintype "passive"))
    )
    (net (code "33") (name "Net-(CON8-VCC)") (class "Default")
      (node (ref "CON8") (pin "3") (pinfunction "VCC_3") (pintype "bidirectional"))
      (node (ref "JP4") (pin "2") (pinfunction "2_2") (pintype "passive"))
    )
    (net (code "34") (name "Net-(R1-P$2)") (class "Default")
      (node (ref "LED2") (pin "A") (pinfunction "A_A") (pintype "passive"))
      (node (ref "R1") (pin "2") (pinfunction "P$2_2") (pintype "passive"))
    )
    (net (code "35") (name "Net-(R2-P$2)") (class "Default")
      (node (ref "LED3") (pin "A") (pinfunction "A_A") (pintype "passive"))
      (node (ref "R2") (pin "2") (pinfunction "P$2_2") (pintype "passive"))
    )
    (net (code "36") (name "Net-(R3-P$2)") (class "Default")
      (node (ref "LED1") (pin "C") (pinfunction "C_C") (pintype "passive"))
      (node (ref "R3") (pin "2") (pinfunction "P$2_2") (pintype "passive"))
    )
    (net (code "37") (name "Net-(R5-P$1)") (class "Default")
      (node (ref "R5") (pin "1") (pinfunction "P$1_1") (pintype "passive"))
      (node (ref "U1") (pin "9") (pinfunction "PIO0_3/USB_VBUS_9") (pintype "bidirectional"))
    )
    (net (code "38") (name "Net-(R9-P$1)") (class "Default")
      (node (ref "R9") (pin "1") (pinfunction "P$1_1") (pintype "passive"))
      (node (ref "T1") (pin "3") (pinfunction "D_3") (pintype "passive"))
    )
    (net (code "39") (name "Net-(R18-P$1)") (class "Default")
      (node (ref "R18") (pin "1") (pinfunction "P$1_1") (pintype "passive"))
      (node (ref "U2") (pin "8") (pinfunction "A1_8") (pintype "input"))
    )
    (net (code "40") (name "Net-(R19-P$1)") (class "Default")
      (node (ref "R19") (pin "1") (pinfunction "P$1_1") (pintype "passive"))
      (node (ref "U2") (pin "7") (pinfunction "A0_7") (pintype "input"))
    )
    (net (code "41") (name "TGT_CTS") (class "Default")
      (node (ref "JP1") (pin "8") (pinfunction "8_8") (pintype "passive"))
      (node (ref "U1") (pin "30") (pinfunction "PIO0_17/~{RTS}/CT32B0_CAP0/SCLK_30") (pintype "bidirectional"))
    )
    (net (code "42") (name "TGT_NRESET") (class "Default")
      (node (ref "CON3") (pin "10") (pinfunction "NRESET_10") (pintype "bidirectional"))
      (node (ref "D3") (pin "A") (pinfunction "A_A") (pintype "passive"))
      (node (ref "JP1") (pin "7") (pinfunction "7_7") (pintype "passive"))
      (node (ref "U1") (pin "8") (pinfunction "PIO0_2/SSEL0/CT16B0_CAP0_8") (pintype "bidirectional"))
    )
    (net (code "43") (name "TGT_NRESET_BUTTON") (class "Default")
      (node (ref "D3") (pin "K") (pinfunction "K_K") (pintype "passive"))
      (node (ref "R7") (pin "2") (pinfunction "P$2_2") (pintype "passive"))
      (node (ref "R8") (pin "2") (pinfunction "P$2_2") (pintype "passive"))
      (node (ref "SW1") (pin "P$2") (pinfunction "S_P$2") (pintype "passive"))
    )
    (net (code "44") (name "TGT_NRESET_FB") (class "Default")
      (node (ref "R7") (pin "1") (pinfunction "P$1_1") (pintype "passive"))
      (node (ref "U1") (pin "3") (pinfunction "PIO0_1/CLKOUT/CT32B0_MAT2/USB_FTOGGLE_3") (pintype "bidirectional"))
    )
    (net (code "45") (name "TGT_NRESET_FB_ISP") (class "Default")
      (node (ref "R8") (pin "1") (pinfunction "P$1_1") (pintype "passive"))
      (node (ref "U1") (pin "1") (pinfunction "PIO1_19/~{DTR}/SSEL1_1") (pintype "bidirectional"))
    )
    (net (code "46") (name "TGT_RTS") (class "Default")
      (node (ref "JP1") (pin "6") (pinfunction "6_6") (pintype "passive"))
      (node (ref "R4") (pin "2") (pinfunction "P$2_2") (pintype "passive"))
      (node (ref "U1") (pin "16") (pinfunction "PIO0_7/~{CTS}_16") (pintype "bidirectional"))
    )
    (net (code "47") (name "TGT_RX") (class "Default")
      (node (ref "CON3") (pin "8") (pinfunction "TGT_RX_8") (pintype "bidirectional"))
      (node (ref "JP1") (pin "11") (pinfunction "11_11") (pintype "passive"))
      (node (ref "U1") (pin "32") (pinfunction "PIO0_19/TXD/CT32B0_MAT1_32") (pintype "bidirectional"))
    )
    (net (code "48") (name "TGT_SWCLK") (class "Default")
      (node (ref "CON3") (pin "4") (pinfunction "SWCLK_4") (pintype "bidirectional"))
      (node (ref "JP1") (pin "3") (pinfunction "3_3") (pintype "passive"))
      (node (ref "R4") (pin "1") (pinfunction "P$1_1") (pintype "passive"))
      (node (ref "U1") (pin "18") (pinfunction "PIO0_9/MOSI0/CT16B0_MAT1_18") (pintype "bidirectional"))
    )
    (net (code "49") (name "TGT_SWDIO") (class "Default")
      (node (ref "CON3") (pin "2") (pinfunction "SWDIO_2") (pintype "bidirectional"))
      (node (ref "JP1") (pin "5") (pinfunction "5_5") (pintype "passive"))
      (node (ref "U1") (pin "17") (pinfunction "PIO0_8/MISO0/CT16B0_MAT0_17") (pintype "bidirectional"))
    )
    (net (code "50") (name "TGT_TX") (class "Default")
      (node (ref "CON3") (pin "7") (pinfunction "TGT_TX_7") (pintype "bidirectional"))
      (node (ref "JP1") (pin "9") (pinfunction "9_9") (pintype "passive"))
      (node (ref "U1") (pin "31") (pinfunction "PIO0_18/RXD/CT32B0_MAT0_31") (pintype "bidirectional"))
    )
    (net (code "51") (name "USB-D+") (class "Default")
      (node (ref "IC1") (pin "4") (pinfunction "IO2_4") (pintype "bidirectional"))
      (node (ref "R11") (pin "1") (pinfunction "P$1_1") (pintype "passive"))
    )
    (net (code "52") (name "USB-D-") (class "Default")
      (node (ref "IC1") (pin "6") (pinfunction "IO1_6") (pintype "bidirectional"))
      (node (ref "R10") (pin "1") (pinfunction "P$1_1") (pintype "passive"))
    )
    (net (code "53") (name "USB-SCON") (class "Default")
      (node (ref "T1") (pin "1") (pinfunction "G_1") (pintype "passive"))
      (node (ref "U1") (pin "15") (pinfunction "PIO0_6/~{USB_CONNECT}/SCK0_15") (pintype "bidirectional"))
    )
    (net (code "54") (name "VIN+") (class "Default")
      (node (ref "JP5") (pin "2") (pinfunction "2_2") (pintype "passive"))
      (node (ref "R13") (pin "2") (pinfunction "P$2_2") (pintype "passive"))
    )
    (net (code "55") (name "VIN-") (class "Default")
      (node (ref "JP5") (pin "1") (pinfunction "1_1") (pintype "passive"))
      (node (ref "R12") (pin "2") (pinfunction "P$2_2") (pintype "passive"))
    )
    (net (code "56") (name "V_ISENSE") (class "Default")
      (node (ref "CON3") (pin "1") (pinfunction "VCC_1") (pintype "bidirectional"))
      (node (ref "JP1") (pin "2") (pinfunction "2_2") (pintype "passive"))
    )
    (net (code "57") (name "unconnected-(CON3-SWO-Pad6)") (class "Default")
      (node (ref "CON3") (pin "6") (pinfunction "SWO_6") (pintype "bidirectional"))
    )
    (net (code "58") (name "unconnected-(CON4-GND-Pad3)") (class "Default")
      (node (ref "CON4") (pin "3") (pinfunction "GND_3") (pintype "bidirectional"))
    )
    (net (code "59") (name "unconnected-(CON4-GND-Pad5)") (class "Default")
      (node (ref "CON4") (pin "5") (pinfunction "GND_5") (pintype "bidirectional"))
    )
    (net (code "60") (name "unconnected-(CON4-SWO-Pad6)") (class "Default")
      (node (ref "CON4") (pin "6") (pinfunction "SWO_6") (pintype "bidirectional"))
    )
    (net (code "61") (name "unconnected-(CON4-TGT_RX-Pad8)") (class "Default")
      (node (ref "CON4") (pin "8") (pinfunction "TGT_RX_8") (pintype "bidirectional"))
    )
    (net (code "62") (name "unconnected-(CON4-TGT_TX-Pad7)") (class "Default")
      (node (ref "CON4") (pin "7") (pinfunction "TGT_TX_7") (pintype "bidirectional"))
    )
    (net (code "63") (name "unconnected-(CON8-A{slash}D1-Pad2)") (class "Default")
      (node (ref "CON8") (pin "2") (pinfunction "A/D1_2") (pintype "bidirectional"))
    )
    (net (code "64") (name "unconnected-(JP1-Pad4)") (class "Default")
      (node (ref "JP1") (pin "4") (pinfunction "4_4") (pintype "passive"))
    )
  )
)
